# Half_H-Bridge_Driver.net
KiCad netlist of a schematic drawn in Altium Designer
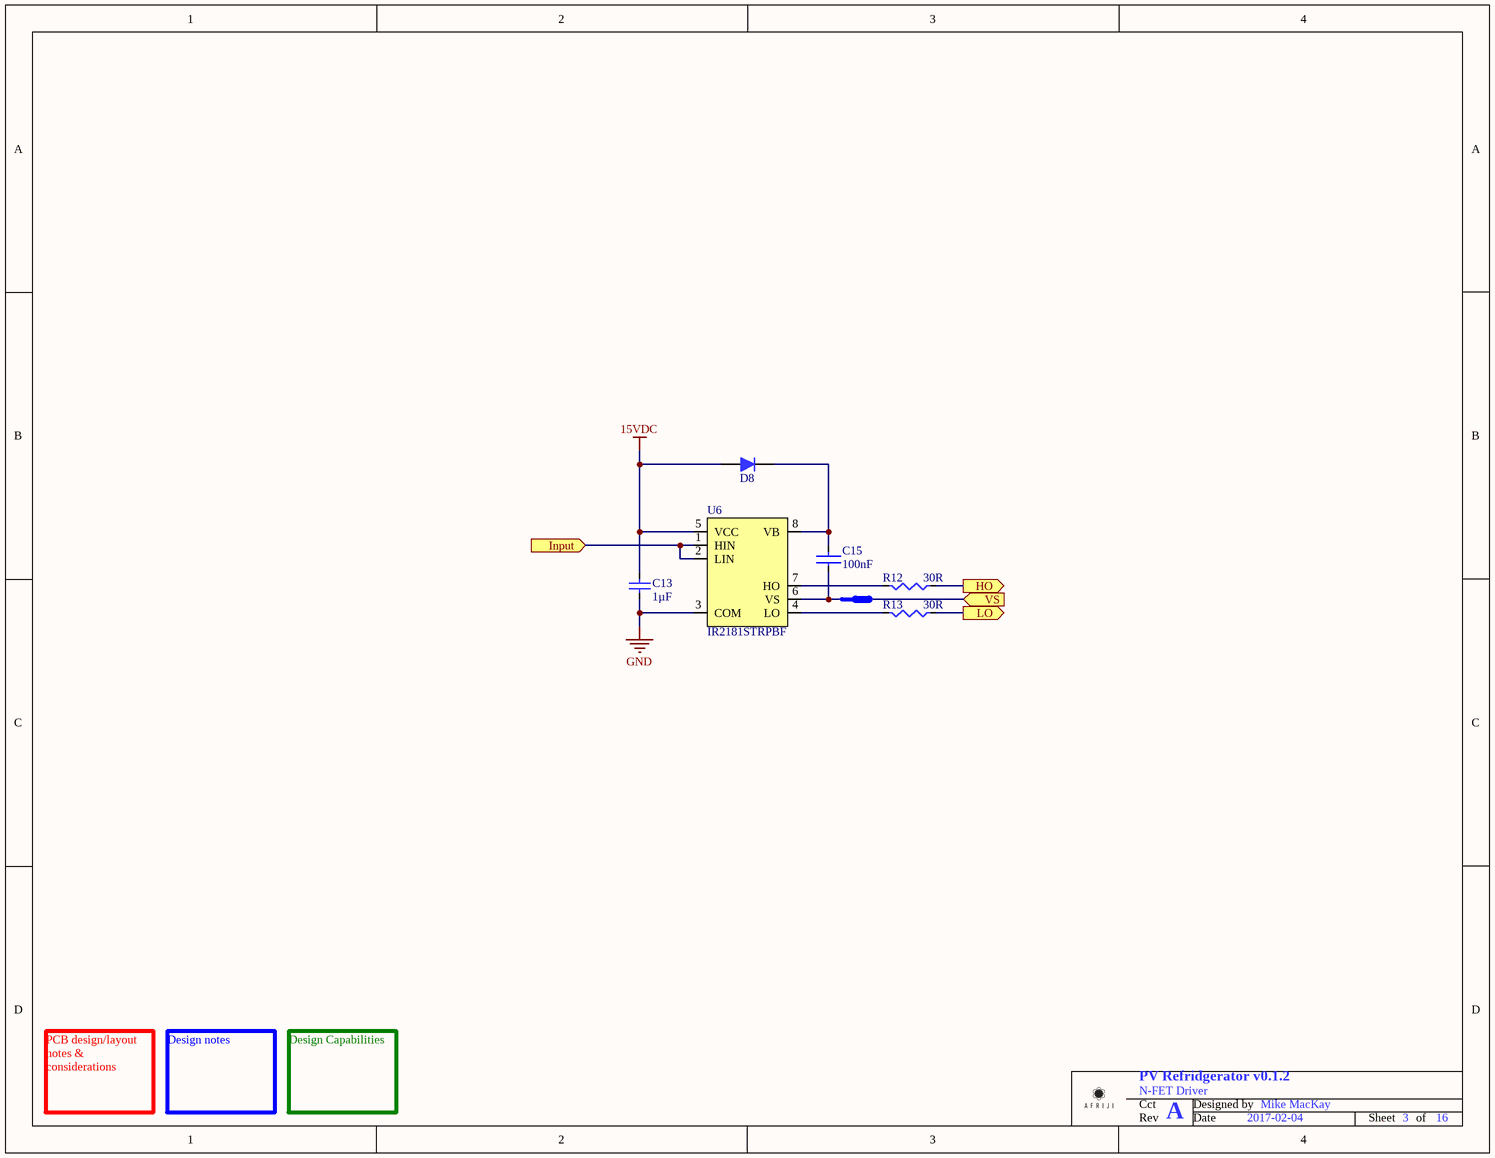
[diagram p0: Half H-Bridge Driver.SchDoc]

(export (version "E")
  (design (tool "Eeschema 10.0.6"))
  (components
    (comp (ref "C13")
      (value "1uF 0603 25V")
      (footprint "Capacitor - 0603 Ceramic")
      (description "Non-polarized")
      (fields
        (field (name "MANUFACTURER") "Murata Electronics North America")
        (field (name "MANUFACTURER PART NUMBER") "GRM188R61E105KA12D")
        (field (name "CAPACITANCE") "1µF")
      )
      (libsource (lib "Integrated Component Library") (part "1uF 0603 25V"))
    )
    (comp (ref "C15")
      (value "100nF 0603 50V")
      (footprint "C0603 - Ceramic")
      (fields
        (field (name "MANUFACTURER") "Samsung Electro-Mechanics America, Inc")
        (field (name "MANUFACTURER PART NUMBER") "CL10B104KB8SFNC")
        (field (name "TOLERANCE") "±10%")
        (field (name "CAPACITANCE") "100nF")
      )
      (libsource (lib "Personal Library") (part "100nF 0603 50V"))
    )
    (comp (ref "D8")
      (value "~")
      (footprint "SMA - Diode")
      (description "Signal Diode")
      (fields
        (field (name "MANUFACTURER") "Vishay Semiconductor Diodes Division")
        (field (name "MANUFACTURER PART NUMBER") "US1G-E3/5AT")
      )
      (libsource (lib "Integrated Component Library") (part "Diode - Signal 1A"))
    )
    (comp (ref "NetTie1")
      (value "Net Tie")
      (footprint "Net tie (7/7 mil)")
      (description "Ties two nets together")
      (libsource (lib "Integrated Component Library") (part "Net Tie"))
    )
    (comp (ref "R12")
      (value "Template - Resistor")
      (footprint "R0603")
      (fields
        (field (name "MANUFACTURER") "Yageo")
        (field (name "MANUFACTURER PART NUMBER") "RC0603FR-0730RL")
        (field (name "RESISTANCE (OHMS)") "30R")
        (field (name "TOLERANCE") "±1%")
      )
      (libsource (lib "Personal Library") (part "Template - Resistor"))
    )
    (comp (ref "R13")
      (value "Template - Resistor")
      (footprint "R0603")
      (fields
        (field (name "MANUFACTURER") "Yageo")
        (field (name "MANUFACTURER PART NUMBER") "RC0603FR-0730RL")
        (field (name "RESISTANCE (OHMS)") "30R")
        (field (name "TOLERANCE") "±1%")
      )
      (libsource (lib "Personal Library") (part "Template - Resistor"))
    )
    (comp (ref "U6")
      (value "H-Bridge Driver")
      (footprint "SOIC-8")
      (fields
        (field (name "MANUFACTURER") "Infineon Technologies")
        (field (name "MANUFACTURER PART NUMBER") "IR2181STRPBF")
      )
      (libsource (lib "Local Library") (part "H-Bridge Driver"))
    )
  )
  (nets
    (net (code "1") (name "/HO") (class "Default")
      (node (ref "R12") (pin "2") (pinfunction "2_2") (pintype "passive"))
    )
    (net (code "2") (name "/Input") (class "Default")
      (node (ref "U6") (pin "1") (pinfunction "HIN_1") (pintype "passive"))
      (node (ref "U6") (pin "2") (pinfunction "LIN_2") (pintype "passive"))
    )
    (net (code "3") (name "/LO") (class "Default")
      (node (ref "R13") (pin "2") (pinfunction "2_2") (pintype "passive"))
    )
    (net (code "4") (name "/VS") (class "Default")
      (node (ref "NetTie1") (pin "2") (pinfunction "2_2") (pintype "passive"))
    )
    (net (code "5") (name "15VDC") (class "Default")
      (node (ref "C13") (pin "1") (pinfunction "1_1") (pintype "passive"))
      (node (ref "D8") (pin "1") (pinfunction "Anode_1") (pintype "passive"))
      (node (ref "U6") (pin "5") (pinfunction "VCC_5") (pintype "passive"))
    )
    (net (code "6") (name "GND") (class "Default")
      (node (ref "C13") (pin "2") (pinfunction "2_2") (pintype "passive"))
      (node (ref "U6") (pin "3") (pinfunction "COM_3") (pintype "passive"))
    )
    (net (code "7") (name "Net-(D8-Cathode)") (class "Default")
      (node (ref "C15") (pin "1") (pinfunction "1_1") (pintype "passive"))
      (node (ref "D8") (pin "2") (pinfunction "Cathode_2") (pintype "passive"))
      (node (ref "U6") (pin "8") (pinfunction "VB_8") (pintype "passive"))
    )
    (net (code "8") (name "Net-(U6-HO)") (class "Default")
      (node (ref "R12") (pin "1") (pinfunction "1_1") (pintype "passive"))
      (node (ref "U6") (pin "7") (pinfunction "HO_7") (pintype "passive"))
    )
    (net (code "9") (name "Net-(U6-LO)") (class "Default")
      (node (ref "R13") (pin "1") (pinfunction "1_1") (pintype "passive"))
      (node (ref "U6") (pin "4") (pinfunction "LO_4") (pintype "passive"))
    )
    (net (code "10") (name "Net-(U6-VS)") (class "Default")
      (node (ref "C15") (pin "2") (pinfunction "2_2") (pintype "passive"))
      (node (ref "NetTie1") (pin "1") (pinfunction "1_1") (pintype "passive"))
      (node (ref "U6") (pin "6") (pinfunction "VS_6") (pintype "passive"))
    )
  )
)
